# MCP2518_PINOUT.net
KiCad netlist of a schematic drawn in Altium Designer
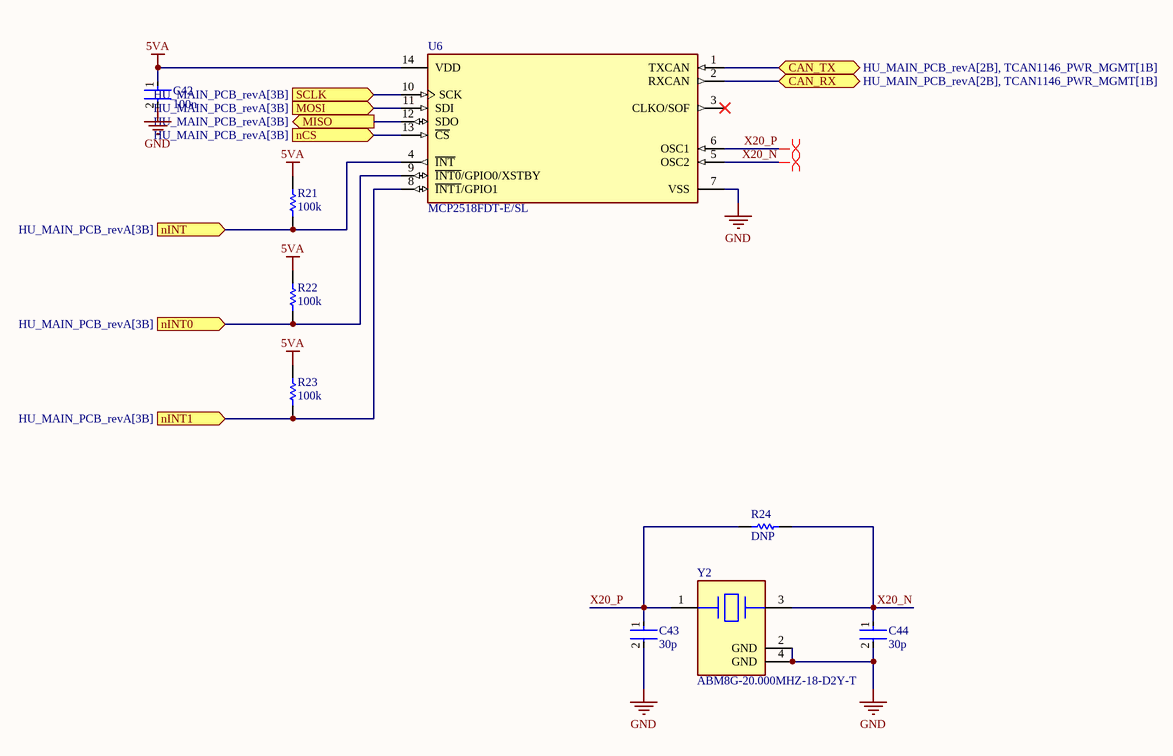
[diagram p0: MCP2518_PINOUT.SchDoc]

(export (version "E")
  (design (tool "Eeschema 10.0.6"))
  (components
    (comp (ref "C42")
      (value "100n")
      (footprint "FP-0402-L_1_0_0_05-W_0_5-IPC_A")
      (description "LARGE PADS, 0402 CAP, CHANGE COMMENT TO MATCH REAL P/N")
      (libsource (lib "Space Concordia") (part "b4654b650e69147ec39a6b967a45e02"))
    )
    (comp (ref "C43")
      (value "30p")
      (footprint "FP-0402-L_1_0_0_05-W_0_5-IPC_A")
      (description "LARGE PADS, 0402 CAP, CHANGE COMMENT TO MATCH REAL P/N")
      (libsource (lib "Space Concordia") (part "b4654b650e69147ec39a6b967a45e02"))
    )
    (comp (ref "C44")
      (value "30p")
      (footprint "FP-0402-L_1_0_0_05-W_0_5-IPC_A")
      (description "LARGE PADS, 0402 CAP, CHANGE COMMENT TO MATCH REAL P/N")
      (libsource (lib "Space Concordia") (part "b4654b650e69147ec39a6b967a45e02"))
    )
    (comp (ref "R21")
      (value "100k")
      (footprint "R0603B")
      (description "Resistor")
      (libsource (lib "Space Concordia") (part "Resistor"))
    )
    (comp (ref "R22")
      (value "100k")
      (footprint "R0603B")
      (description "Resistor")
      (libsource (lib "Space Concordia") (part "Resistor"))
    )
    (comp (ref "R23")
      (value "100k")
      (footprint "R0603B")
      (description "Resistor")
      (libsource (lib "Space Concordia") (part "Resistor"))
    )
    (comp (ref "R24")
      (value "DNP")
      (footprint "R0603B")
      (description "Resistor")
      (libsource (lib "Space Concordia") (part "Resistor"))
    )
    (comp (ref "U6")
      (value "MCP2518FDT-E/SL")
      (footprint "FP-C04-065-SL-IPC_C")
      (description "IC CAN CONTROLLER SPI 14SOIC")
      (libsource (lib "Altium Content Vault") (part "48378335c028dfc4faaf2298fb5e2a1"))
    )
    (comp (ref "Y2")
      (value "ABM8G-20.000MHZ-18-D2Y-T")
      (footprint "FP-ABM8G-MFG")
      (description "Crystal 20MHz ±20ppm (Tol) ±30ppm (Stability) 18pF FUND 80Ω 4-Pin SMD T/R")
      (fields (field (name "TOLERANCE") "20ppm"))
      (libsource (lib "Altium Content Vault") (part "48e526d86b7f2615d98721063c72f49"))
    )
  )
  (nets
    (net (code "1") (name "/CAN_RX") (class "Default")
      (node (ref "U6") (pin "2") (pinfunction "RXCAN_2") (pintype "output"))
    )
    (net (code "2") (name "/CAN_TX") (class "Default")
      (node (ref "U6") (pin "1") (pinfunction "TXCAN_1") (pintype "input"))
    )
    (net (code "3") (name "/MISO") (class "Default")
      (node (ref "U6") (pin "12") (pinfunction "SDO_12") (pintype "bidirectional"))
    )
    (net (code "4") (name "/MOSI") (class "Default")
      (node (ref "U6") (pin "11") (pinfunction "SDI_11") (pintype "input"))
    )
    (net (code "5") (name "/SCLK") (class "Default")
      (node (ref "U6") (pin "10") (pinfunction "SCK_10") (pintype "input"))
    )
    (net (code "6") (name "/X20_N") (class "Default")
      (node (ref "C44") (pin "1") (pinfunction "1_1") (pintype "passive"))
      (node (ref "R24") (pin "2") (pinfunction "2_2") (pintype "passive"))
      (node (ref "U6") (pin "5") (pinfunction "OSC2_5") (pintype "input"))
      (node (ref "Y2") (pin "3") (pinfunction "3_3") (pintype "passive"))
    )
    (net (code "7") (name "/X20_P") (class "Default")
      (node (ref "C43") (pin "1") (pinfunction "1_1") (pintype "passive"))
      (node (ref "R24") (pin "1") (pinfunction "1_1") (pintype "passive"))
      (node (ref "U6") (pin "6") (pinfunction "OSC1_6") (pintype "input"))
      (node (ref "Y2") (pin "1") (pinfunction "1_1") (pintype "passive"))
    )
    (net (code "8") (name "/nCS") (class "Default")
      (node (ref "U6") (pin "13") (pinfunction "~{CS}_13") (pintype "input"))
    )
    (net (code "9") (name "/nINT") (class "Default")
      (node (ref "R21") (pin "2") (pinfunction "2_2") (pintype "passive"))
      (node (ref "U6") (pin "4") (pinfunction "~{INT}_4") (pintype "output"))
    )
    (net (code "10") (name "/nINT0") (class "Default")
      (node (ref "R22") (pin "2") (pinfunction "2_2") (pintype "passive"))
      (node (ref "U6") (pin "9") (pinfunction "~{INT0}/GPIO0/XSTBY_9") (pintype "bidirectional"))
    )
    (net (code "11") (name "/nINT1") (class "Default")
      (node (ref "R23") (pin "2") (pinfunction "2_2") (pintype "passive"))
      (node (ref "U6") (pin "8") (pinfunction "~{INT1}/GPIO1_8") (pintype "bidirectional"))
    )
    (net (code "12") (name "5VA") (class "Default")
      (node (ref "C42") (pin "1") (pinfunction "1_1") (pintype "passive"))
      (node (ref "R21") (pin "1") (pinfunction "1_1") (pintype "passive"))
      (node (ref "R22") (pin "1") (pinfunction "1_1") (pintype "passive"))
      (node (ref "R23") (pin "1") (pinfunction "1_1") (pintype "passive"))
      (node (ref "U6") (pin "14") (pinfunction "VDD_14") (pintype "power_in"))
    )
    (net (code "13") (name "GND") (class "Default")
      (node (ref "C42") (pin "2") (pinfunction "2_2") (pintype "passive"))
      (node (ref "C43") (pin "2") (pinfunction "2_2") (pintype "passive"))
      (node (ref "C44") (pin "2") (pinfunction "2_2") (pintype "passive"))
      (node (ref "U6") (pin "7") (pinfunction "VSS_7") (pintype "power_in"))
      (node (ref "Y2") (pin "2") (pinfunction "GND_2") (pintype "power_in"))
      (node (ref "Y2") (pin "4") (pinfunction "GND_4") (pintype "power_in"))
    )
    (net (code "14") (name "unconnected-(U6-CLKO{slash}SOF-Pad3)") (class "Default")
      (node (ref "U6") (pin "3") (pinfunction "CLKO/SOF_3") (pintype "output+no_connect"))
    )
  )
)
